# mcuBoard.net
KiCad netlist of a schematic drawn in EAGLE
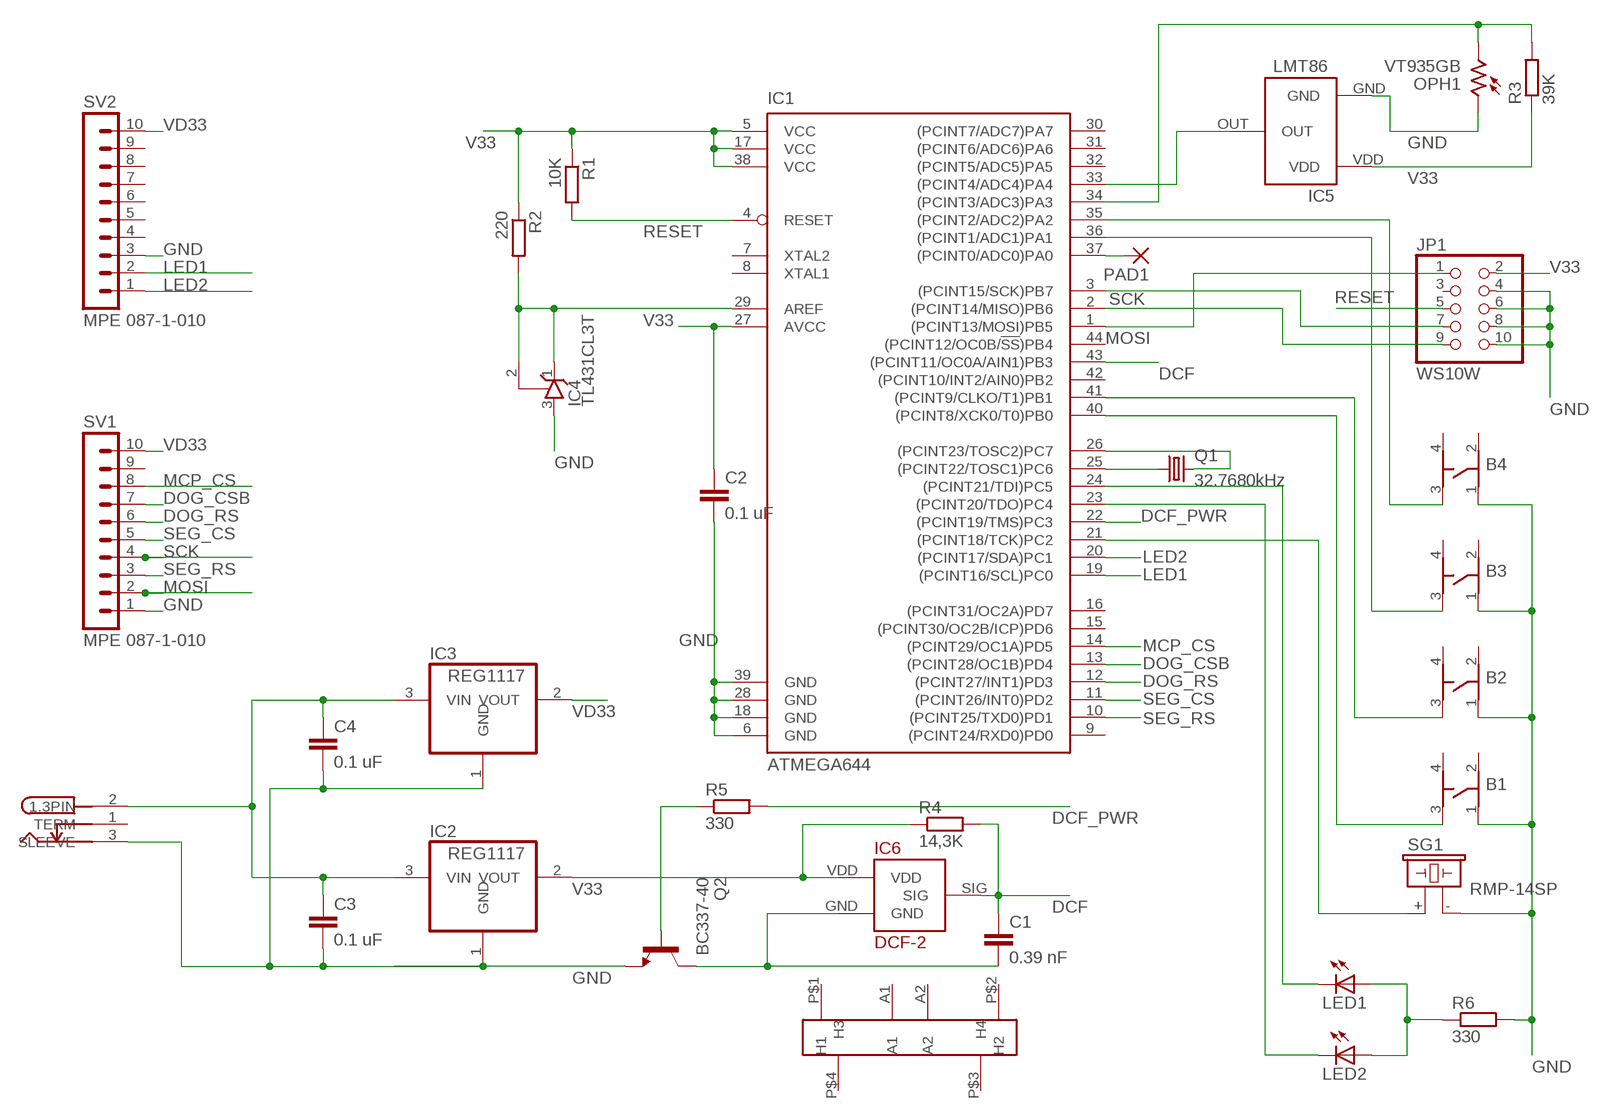
[diagram p0: schematic, sheet 1]

(export (version "E")
  (design (tool "Eeschema 10.0.6"))
  (components
    (comp (ref "B1")
      (value "BUTTON-D6X")
      (footprint "eagle-import:BUTTON-D6X")
      (libsource (lib "eagle-import") (part "BUTTON-D6X"))
    )
    (comp (ref "B2")
      (value "BUTTON-D6X")
      (footprint "eagle-import:BUTTON-D6X")
      (libsource (lib "eagle-import") (part "BUTTON-D6X"))
    )
    (comp (ref "B3")
      (value "BUTTON-D6X")
      (footprint "eagle-import:BUTTON-D6X")
      (libsource (lib "eagle-import") (part "BUTTON-D6X"))
    )
    (comp (ref "B4")
      (value "BUTTON-D6X")
      (footprint "eagle-import:BUTTON-D6X")
      (libsource (lib "eagle-import") (part "BUTTON-D6X"))
    )
    (comp (ref "C1")
      (value "0.39 nF")
      (footprint "eagle-import:C1206")
      (libsource (lib "eagle-import") (part "C-EUC1206"))
    )
    (comp (ref "C2")
      (value "0.1 uF")
      (footprint "eagle-import:C1206K")
      (libsource (lib "eagle-import") (part "C-EUC1206K"))
    )
    (comp (ref "C3")
      (value "0.1 uF")
      (footprint "eagle-import:C1206K")
      (libsource (lib "eagle-import") (part "C-EUC1206K"))
    )
    (comp (ref "C4")
      (value "0.1 uF")
      (footprint "eagle-import:C1206K")
      (libsource (lib "eagle-import") (part "C-EUC1206K"))
    )
    (comp (ref "IC1")
      (value "ATMEGA644")
      (footprint "eagle-import:TQFP44")
      (fields (field (name "MPN") "ATMEGA644PV-10AU"))
      (libsource (lib "eagle-import") (part "ATMEGA644A"))
    )
    (comp (ref "IC2")
      (value "REG1117")
      (footprint "eagle-import:SOT223")
      (libsource (lib "eagle-import") (part "REG1117"))
    )
    (comp (ref "IC3")
      (value "REG1117")
      (footprint "eagle-import:SOT223")
      (libsource (lib "eagle-import") (part "REG1117"))
    )
    (comp (ref "IC4")
      (value "TL431CL3T")
      (footprint "eagle-import:SOT23")
      (libsource (lib "eagle-import") (part "TL431CL3T"))
    )
    (comp (ref "IC5")
      (value "LMT86")
      (footprint "eagle-import:LMT86")
      (libsource (lib "eagle-import") (part "LMT86"))
    )
    (comp (ref "IC6")
      (value "DCF77")
      (footprint "eagle-import:DCF77")
      (libsource (lib "eagle-import") (part "DCF77"))
    )
    (comp (ref "JP1")
      (value "WS10W")
      (footprint "eagle-import:2X05")
      (libsource (lib "eagle-import") (part "PINHD-2X5"))
    )
    (comp (ref "LED1")
      (value "LED3MM")
      (footprint "eagle-import:LED3MM")
      (libsource (lib "eagle-import") (part "LED3MM"))
    )
    (comp (ref "LED2")
      (value "LED3MM")
      (footprint "eagle-import:LED3MM")
      (libsource (lib "eagle-import") (part "LED3MM"))
    )
    (comp (ref "OPH1")
      (value "VT935GB")
      (footprint "eagle-import:VT900")
      (libsource (lib "eagle-import") (part "VT935GB"))
    )
    (comp (ref "PAD1")
      (value "1,6/0,8")
      (footprint "eagle-import:1,6_0,8")
      (libsource (lib "eagle-import") (part "1,6/0,8"))
    )
    (comp (ref "Q1")
      (value "32.7680kHz")
      (footprint "eagle-import:MC-306")
      (fields (field (name "MPN") "MC-306 60.0KHZ  100PPM ,12.5PF"))
      (libsource (lib "eagle-import") (part "MC-306"))
    )
    (comp (ref "Q2")
      (value "BC337-40")
      (footprint "eagle-import:TO92")
      (libsource (lib "eagle-import") (part "BC337-40"))
    )
    (comp (ref "R1")
      (value "10K")
      (footprint "eagle-import:M1206")
      (libsource (lib "eagle-import") (part "R-EU_M1206"))
    )
    (comp (ref "R2")
      (value "220")
      (footprint "eagle-import:M1206")
      (libsource (lib "eagle-import") (part "R-EU_M1206"))
    )
    (comp (ref "R3")
      (value "39K")
      (footprint "eagle-import:M1206")
      (libsource (lib "eagle-import") (part "R-EU_M1206"))
    )
    (comp (ref "R4")
      (value "14,3K")
      (footprint "eagle-import:R1206")
      (libsource (lib "eagle-import") (part "R-EU_R1206"))
    )
    (comp (ref "R5")
      (value "330")
      (footprint "eagle-import:R1206")
      (libsource (lib "eagle-import") (part "R-EU_R1206"))
    )
    (comp (ref "R6")
      (value "330")
      (footprint "eagle-import:M1206")
      (libsource (lib "eagle-import") (part "R-EU_M1206"))
    )
    (comp (ref "SG1")
      (value "RMP-14SP")
      (footprint "eagle-import:F_CM12P")
      (libsource (lib "eagle-import") (part "F/CM12P"))
    )
    (comp (ref "SV1")
      (value "MPE 087-1-010")
      (footprint "eagle-import:MA10-1")
      (libsource (lib "eagle-import") (part "MA10-1"))
    )
    (comp (ref "SV2")
      (value "MPE 087-1-010")
      (footprint "eagle-import:MA10-1")
      (libsource (lib "eagle-import") (part "MA10-1"))
    )
    (comp (ref "U$1")
      (value "DC-8N")
      (footprint "eagle-import:BUCHSE-1.3X3.75")
      (libsource (lib "eagle-import") (part "DC-8N"))
    )
    (comp (ref "U$2")
      (value "DCF77-ANT")
      (footprint "eagle-import:DCF77-ANT")
      (libsource (lib "eagle-import") (part "DCF77-ANT"))
    )
  )
  (nets
    (net (code "1") (name "/DCF") (class "Default")
      (node (ref "C1") (pin "1") (pinfunction "1_1") (pintype "passive"))
      (node (ref "IC1") (pin "43") (pinfunction "(PCINT11/OC0A/AIN1)PB3_43") (pintype "bidirectional"))
      (node (ref "IC6") (pin "SIG") (pinfunction "SIG_SIG") (pintype "bidirectional"))
      (node (ref "R4") (pin "2") (pinfunction "2_2") (pintype "passive"))
    )
    (net (code "2") (name "/DCF_PWR") (class "Default")
      (node (ref "IC1") (pin "22") (pinfunction "(PCINT19/TMS)PC3_22") (pintype "output"))
      (node (ref "R5") (pin "2") (pinfunction "2_2") (pintype "passive"))
    )
    (net (code "3") (name "/DOG_CSB") (class "Default")
      (node (ref "IC1") (pin "13") (pinfunction "(PCINT28/OC1B)PD4_13") (pintype "bidirectional"))
      (node (ref "SV1") (pin "7") (pinfunction "7_7") (pintype "passive"))
    )
    (net (code "4") (name "/DOG_RS") (class "Default")
      (node (ref "IC1") (pin "12") (pinfunction "(PCINT27/INT1)PD3_12") (pintype "bidirectional"))
      (node (ref "SV1") (pin "6") (pinfunction "6_6") (pintype "passive"))
    )
    (net (code "5") (name "/GND") (class "Default")
      (node (ref "B1") (pin "1") (pinfunction "1_1") (pintype "bidirectional"))
      (node (ref "B2") (pin "1") (pinfunction "1_1") (pintype "bidirectional"))
      (node (ref "B3") (pin "1") (pinfunction "1_1") (pintype "bidirectional"))
      (node (ref "B4") (pin "1") (pinfunction "1_1") (pintype "bidirectional"))
      (node (ref "C2") (pin "2") (pinfunction "2_2") (pintype "passive"))
      (node (ref "C3") (pin "2") (pinfunction "2_2") (pintype "passive"))
      (node (ref "C4") (pin "2") (pinfunction "2_2") (pintype "passive"))
      (node (ref "IC1") (pin "18") (pinfunction "GND_18") (pintype "power_in"))
      (node (ref "IC1") (pin "28") (pinfunction "GND_28") (pintype "power_in"))
      (node (ref "IC1") (pin "39") (pinfunction "GND_39") (pintype "power_in"))
      (node (ref "IC1") (pin "6") (pinfunction "GND_6") (pintype "power_in"))
      (node (ref "IC2") (pin "1") (pinfunction "GND_1") (pintype "power_in"))
      (node (ref "IC3") (pin "1") (pinfunction "GND_1") (pintype "power_in"))
      (node (ref "IC4") (pin "3") (pinfunction "A_3") (pintype "passive"))
      (node (ref "IC5") (pin "GND") (pinfunction "GND_GND") (pintype "power_in"))
      (node (ref "JP1") (pin "10") (pinfunction "10_10") (pintype "passive"))
      (node (ref "JP1") (pin "4") (pinfunction "4_4") (pintype "passive"))
      (node (ref "JP1") (pin "6") (pinfunction "6_6") (pintype "passive"))
      (node (ref "JP1") (pin "8") (pinfunction "8_8") (pintype "passive"))
      (node (ref "OPH1") (pin "1") (pinfunction "1_1") (pintype "passive"))
      (node (ref "Q2") (pin "1") (pinfunction "E_1") (pintype "passive"))
      (node (ref "R6") (pin "2") (pinfunction "2_2") (pintype "passive"))
      (node (ref "SG1") (pin "-") (pinfunction "2_-") (pintype "passive"))
      (node (ref "SV1") (pin "1") (pinfunction "1_1") (pintype "passive"))
      (node (ref "SV2") (pin "3") (pinfunction "3_3") (pintype "passive"))
      (node (ref "U$1") (pin "3") (pinfunction "SLEEVE_3") (pintype "power_in"))
    )
    (net (code "6") (name "/LED1") (class "Default")
      (node (ref "IC1") (pin "19") (pinfunction "(PCINT16/SCL)PC0_19") (pintype "output"))
      (node (ref "SV2") (pin "2") (pinfunction "2_2") (pintype "passive"))
    )
    (net (code "7") (name "/LED2") (class "Default")
      (node (ref "IC1") (pin "20") (pinfunction "(PCINT17/SDA)PC1_20") (pintype "output"))
      (node (ref "SV2") (pin "1") (pinfunction "1_1") (pintype "passive"))
    )
    (net (code "8") (name "/MCP_CS") (class "Default")
      (node (ref "IC1") (pin "14") (pinfunction "(PCINT29/OC1A)PD5_14") (pintype "bidirectional"))
      (node (ref "SV1") (pin "8") (pinfunction "8_8") (pintype "passive"))
    )
    (net (code "9") (name "/MOSI") (class "Default")
      (node (ref "IC1") (pin "1") (pinfunction "(PCINT13/MOSI)PB5_1") (pintype "bidirectional"))
      (node (ref "JP1") (pin "1") (pinfunction "1_1") (pintype "passive"))
      (node (ref "SV1") (pin "2") (pinfunction "2_2") (pintype "passive"))
    )
    (net (code "10") (name "/RESET") (class "Default")
      (node (ref "IC1") (pin "4") (pinfunction "RESET_4") (pintype "input"))
      (node (ref "JP1") (pin "5") (pinfunction "5_5") (pintype "passive"))
      (node (ref "R1") (pin "2") (pinfunction "2_2") (pintype "passive"))
    )
    (net (code "11") (name "/SCK") (class "Default")
      (node (ref "IC1") (pin "3") (pinfunction "(PCINT15/SCK)PB7_3") (pintype "bidirectional"))
      (node (ref "JP1") (pin "7") (pinfunction "7_7") (pintype "passive"))
      (node (ref "SV1") (pin "4") (pinfunction "4_4") (pintype "passive"))
    )
    (net (code "12") (name "/SEG_CS") (class "Default")
      (node (ref "IC1") (pin "11") (pinfunction "(PCINT26/INT0)PD2_11") (pintype "bidirectional"))
      (node (ref "SV1") (pin "5") (pinfunction "5_5") (pintype "passive"))
    )
    (net (code "13") (name "/SEG_RS") (class "Default")
      (node (ref "IC1") (pin "10") (pinfunction "(PCINT25/TXD0)PD1_10") (pintype "bidirectional"))
      (node (ref "SV1") (pin "3") (pinfunction "3_3") (pintype "passive"))
    )
    (net (code "14") (name "/V33") (class "Default")
      (node (ref "C2") (pin "1") (pinfunction "1_1") (pintype "passive"))
      (node (ref "IC1") (pin "17") (pinfunction "VCC_17") (pintype "power_in"))
      (node (ref "IC1") (pin "27") (pinfunction "AVCC_27") (pintype "power_in"))
      (node (ref "IC1") (pin "38") (pinfunction "VCC_38") (pintype "power_in"))
      (node (ref "IC1") (pin "5") (pinfunction "VCC_5") (pintype "power_in"))
      (node (ref "IC2") (pin "2") (pinfunction "VOUT_2") (pintype "output"))
      (node (ref "IC5") (pin "VDD") (pinfunction "VDD_VDD") (pintype "power_in"))
      (node (ref "IC6") (pin "VDD") (pinfunction "VDD_VDD") (pintype "power_in"))
      (node (ref "JP1") (pin "2") (pinfunction "2_2") (pintype "passive"))
      (node (ref "R1") (pin "1") (pinfunction "1_1") (pintype "passive"))
      (node (ref "R2") (pin "1") (pinfunction "1_1") (pintype "passive"))
      (node (ref "R3") (pin "1") (pinfunction "1_1") (pintype "passive"))
      (node (ref "R4") (pin "1") (pinfunction "1_1") (pintype "passive"))
    )
    (net (code "15") (name "/VD33") (class "Default")
      (node (ref "IC3") (pin "2") (pinfunction "VOUT_2") (pintype "output"))
      (node (ref "SV1") (pin "10") (pinfunction "10_10") (pintype "passive"))
      (node (ref "SV2") (pin "10") (pinfunction "10_10") (pintype "passive"))
    )
    (net (code "16") (name "Net-(IC1-(PCINT0{slash}ADC0)PA0)") (class "Default")
      (node (ref "IC1") (pin "37") (pinfunction "(PCINT0/ADC0)PA0_37") (pintype "bidirectional"))
      (node (ref "PAD1") (pin "1") (pinfunction "P_1") (pintype "passive"))
    )
    (net (code "17") (name "Net-(IC1-(PCINT1{slash}ADC1)PA1)") (class "Default")
      (node (ref "B3") (pin "3") (pinfunction "3_3") (pintype "bidirectional"))
      (node (ref "IC1") (pin "36") (pinfunction "(PCINT1/ADC1)PA1_36") (pintype "bidirectional"))
    )
    (net (code "18") (name "Net-(IC1-(PCINT2{slash}ADC2)PA2)") (class "Default")
      (node (ref "B4") (pin "3") (pinfunction "3_3") (pintype "bidirectional"))
      (node (ref "IC1") (pin "35") (pinfunction "(PCINT2/ADC2)PA2_35") (pintype "bidirectional"))
    )
    (net (code "19") (name "Net-(IC1-(PCINT3{slash}ADC3)PA3)") (class "Default")
      (node (ref "IC1") (pin "34") (pinfunction "(PCINT3/ADC3)PA3_34") (pintype "bidirectional"))
      (node (ref "OPH1") (pin "2") (pinfunction "2_2") (pintype "passive"))
      (node (ref "R3") (pin "2") (pinfunction "2_2") (pintype "passive"))
    )
    (net (code "20") (name "Net-(IC1-(PCINT4{slash}ADC4)PA4)") (class "Default")
      (node (ref "IC1") (pin "33") (pinfunction "(PCINT4/ADC4)PA4_33") (pintype "bidirectional"))
      (node (ref "IC5") (pin "OUT") (pinfunction "OUT_OUT") (pintype "bidirectional"))
    )
    (net (code "21") (name "Net-(IC1-(PCINT8{slash}XCK0{slash}T0)PB0)") (class "Default")
      (node (ref "B1") (pin "3") (pinfunction "3_3") (pintype "bidirectional"))
      (node (ref "IC1") (pin "40") (pinfunction "(PCINT8/XCK0/T0)PB0_40") (pintype "bidirectional"))
    )
    (net (code "22") (name "Net-(IC1-(PCINT9{slash}CLKO{slash}T1)PB1)") (class "Default")
      (node (ref "B2") (pin "3") (pinfunction "3_3") (pintype "bidirectional"))
      (node (ref "IC1") (pin "41") (pinfunction "(PCINT9/CLKO/T1)PB1_41") (pintype "bidirectional"))
    )
    (net (code "23") (name "Net-(IC1-(PCINT14{slash}MISO)PB6)") (class "Default")
      (node (ref "IC1") (pin "2") (pinfunction "(PCINT14/MISO)PB6_2") (pintype "bidirectional"))
      (node (ref "JP1") (pin "9") (pinfunction "9_9") (pintype "passive"))
    )
    (net (code "24") (name "Net-(IC1-(PCINT18{slash}TCK)PC2)") (class "Default")
      (node (ref "IC1") (pin "21") (pinfunction "(PCINT18/TCK)PC2_21") (pintype "output"))
      (node (ref "SG1") (pin "+") (pinfunction "1_+") (pintype "passive"))
    )
    (net (code "25") (name "Net-(IC1-(PCINT20{slash}TDO)PC4)") (class "Default")
      (node (ref "IC1") (pin "23") (pinfunction "(PCINT20/TDO)PC4_23") (pintype "output"))
      (node (ref "LED2") (pin "K") (pinfunction "C_K") (pintype "passive"))
    )
    (net (code "26") (name "Net-(IC1-(PCINT21{slash}TDI)PC5)") (class "Default")
      (node (ref "IC1") (pin "24") (pinfunction "(PCINT21/TDI)PC5_24") (pintype "output"))
      (node (ref "LED1") (pin "K") (pinfunction "C_K") (pintype "passive"))
    )
    (net (code "27") (name "Net-(IC1-(PCINT22{slash}TOSC1)PC6)") (class "Default")
      (node (ref "IC1") (pin "25") (pinfunction "(PCINT22/TOSC1)PC6_25") (pintype "output"))
      (node (ref "Q1") (pin "1") (pinfunction "1_1") (pintype "passive"))
    )
    (net (code "28") (name "Net-(IC1-(PCINT23{slash}TOSC2)PC7)") (class "Default")
      (node (ref "IC1") (pin "26") (pinfunction "(PCINT23/TOSC2)PC7_26") (pintype "output"))
      (node (ref "Q1") (pin "4") (pinfunction "2_4") (pintype "passive"))
    )
    (net (code "29") (name "Net-(IC1-AREF)") (class "Default")
      (node (ref "IC1") (pin "29") (pinfunction "AREF_29") (pintype "passive"))
      (node (ref "IC4") (pin "1") (pinfunction "C_1") (pintype "passive"))
      (node (ref "IC4") (pin "2") (pinfunction "R_2") (pintype "passive"))
      (node (ref "R2") (pin "2") (pinfunction "2_2") (pintype "passive"))
    )
    (net (code "30") (name "Net-(IC2-VIN)") (class "Default")
      (node (ref "C3") (pin "1") (pinfunction "1_1") (pintype "passive"))
      (node (ref "C4") (pin "1") (pinfunction "1_1") (pintype "passive"))
      (node (ref "IC2") (pin "3") (pinfunction "VIN_3") (pintype "input"))
      (node (ref "IC3") (pin "3") (pinfunction "VIN_3") (pintype "input"))
      (node (ref "U$1") (pin "2") (pinfunction "1.3PIN_2") (pintype "power_in"))
    )
    (net (code "31") (name "Net-(LED1-PadA)") (class "Default")
      (node (ref "LED1") (pin "A") (pinfunction "A_A") (pintype "passive"))
      (node (ref "LED2") (pin "A") (pinfunction "A_A") (pintype "passive"))
      (node (ref "R6") (pin "1") (pinfunction "1_1") (pintype "passive"))
    )
    (net (code "32") (name "Net-(Q2-B)") (class "Default")
      (node (ref "Q2") (pin "2") (pinfunction "B_2") (pintype "passive"))
      (node (ref "R5") (pin "1") (pinfunction "1_1") (pintype "passive"))
    )
    (net (code "33") (name "Net-(Q2-C)") (class "Default")
      (node (ref "C1") (pin "2") (pinfunction "2_2") (pintype "passive"))
      (node (ref "IC6") (pin "GND") (pinfunction "GND_GND") (pintype "power_in"))
      (node (ref "Q2") (pin "3") (pinfunction "C_3") (pintype "passive"))
    )
    (net (code "34") (name "unconnected-(B1-Pad2)") (class "Default")
      (node (ref "B1") (pin "2") (pinfunction "2_2") (pintype "bidirectional"))
    )
    (net (code "35") (name "unconnected-(B1-Pad4)") (class "Default")
      (node (ref "B1") (pin "4") (pinfunction "4_4") (pintype "bidirectional"))
    )
    (net (code "36") (name "unconnected-(B2-Pad2)") (class "Default")
      (node (ref "B2") (pin "2") (pinfunction "2_2") (pintype "bidirectional"))
    )
    (net (code "37") (name "unconnected-(B2-Pad4)") (class "Default")
      (node (ref "B2") (pin "4") (pinfunction "4_4") (pintype "bidirectional"))
    )
    (net (code "38") (name "unconnected-(B3-Pad2)") (class "Default")
      (node (ref "B3") (pin "2") (pinfunction "2_2") (pintype "bidirectional"))
    )
    (net (code "39") (name "unconnected-(B3-Pad4)") (class "Default")
      (node (ref "B3") (pin "4") (pinfunction "4_4") (pintype "bidirectional"))
    )
    (net (code "40") (name "unconnected-(B4-Pad2)") (class "Default")
      (node (ref "B4") (pin "2") (pinfunction "2_2") (pintype "bidirectional"))
    )
    (net (code "41") (name "unconnected-(B4-Pad4)") (class "Default")
      (node (ref "B4") (pin "4") (pinfunction "4_4") (pintype "bidirectional"))
    )
    (net (code "42") (name "unconnected-(IC1-(PCINT5{slash}ADC5)PA5-Pad32)") (class "Default")
      (node (ref "IC1") (pin "32") (pinfunction "(PCINT5/ADC5)PA5_32") (pintype "bidirectional"))
    )
    (net (code "43") (name "unconnected-(IC1-(PCINT6{slash}ADC6)PA6-Pad31)") (class "Default")
      (node (ref "IC1") (pin "31") (pinfunction "(PCINT6/ADC6)PA6_31") (pintype "bidirectional"))
    )
    (net (code "44") (name "unconnected-(IC1-(PCINT7{slash}ADC7)PA7-Pad30)") (class "Default")
      (node (ref "IC1") (pin "30") (pinfunction "(PCINT7/ADC7)PA7_30") (pintype "bidirectional"))
    )
    (net (code "45") (name "unconnected-(IC1-(PCINT10{slash}INT2{slash}AIN0)PB2-Pad42)") (class "Default")
      (node (ref "IC1") (pin "42") (pinfunction "(PCINT10/INT2/AIN0)PB2_42") (pintype "bidirectional"))
    )
    (net (code "46") (name "unconnected-(IC1-(PCINT12{slash}OC0B{slash}~{SS})PB4-Pad44)") (class "Default")
      (node (ref "IC1") (pin "44") (pinfunction "(PCINT12/OC0B/~{SS})PB4_44") (pintype "bidirectional"))
    )
    (net (code "47") (name "unconnected-(IC1-(PCINT24{slash}RXD0)PD0-Pad9)") (class "Default")
      (node (ref "IC1") (pin "9") (pinfunction "(PCINT24/RXD0)PD0_9") (pintype "bidirectional"))
    )
    (net (code "48") (name "unconnected-(IC1-(PCINT30{slash}OC2B{slash}ICP)PD6-Pad15)") (class "Default")
      (node (ref "IC1") (pin "15") (pinfunction "(PCINT30/OC2B/ICP)PD6_15") (pintype "bidirectional"))
    )
    (net (code "49") (name "unconnected-(IC1-(PCINT31{slash}OC2A)PD7-Pad16)") (class "Default")
      (node (ref "IC1") (pin "16") (pinfunction "(PCINT31/OC2A)PD7_16") (pintype "bidirectional"))
    )
    (net (code "50") (name "unconnected-(IC1-XTAL1-Pad8)") (class "Default")
      (node (ref "IC1") (pin "8") (pinfunction "XTAL1_8") (pintype "bidirectional"))
    )
    (net (code "51") (name "unconnected-(IC1-XTAL2-Pad7)") (class "Default")
      (node (ref "IC1") (pin "7") (pinfunction "XTAL2_7") (pintype "bidirectional"))
    )
    (net (code "52") (name "unconnected-(JP1-Pad3)") (class "Default")
      (node (ref "JP1") (pin "3") (pinfunction "3_3") (pintype "passive"))
    )
    (net (code "53") (name "unconnected-(SV1-Pad9)") (class "Default")
      (node (ref "SV1") (pin "9") (pinfunction "9_9") (pintype "passive"))
    )
    (net (code "54") (name "unconnected-(SV2-Pad4)") (class "Default")
      (node (ref "SV2") (pin "4") (pinfunction "4_4") (pintype "passive"))
    )
    (net (code "55") (name "unconnected-(SV2-Pad5)") (class "Default")
      (node (ref "SV2") (pin "5") (pinfunction "5_5") (pintype "passive"))
    )
    (net (code "56") (name "unconnected-(SV2-Pad6)") (class "Default")
      (node (ref "SV2") (pin "6") (pinfunction "6_6") (pintype "passive"))
    )
    (net (code "57") (name "unconnected-(SV2-Pad7)") (class "Default")
      (node (ref "SV2") (pin "7") (pinfunction "7_7") (pintype "passive"))
    )
    (net (code "58") (name "unconnected-(SV2-Pad8)") (class "Default")
      (node (ref "SV2") (pin "8") (pinfunction "8_8") (pintype "passive"))
    )
    (net (code "59") (name "unconnected-(SV2-Pad9)") (class "Default")
      (node (ref "SV2") (pin "9") (pinfunction "9_9") (pintype "passive"))
    )
    (net (code "60") (name "unconnected-(U$1-TERM-Pad1)") (class "Default")
      (node (ref "U$1") (pin "1") (pinfunction "TERM_1") (pintype "bidirectional"))
    )
    (net (code "61") (name "unconnected-(U$2-H1-PadP$1)") (class "Default")
      (node (ref "U$2") (pin "P$1") (pinfunction "H1_P$1") (pintype "bidirectional"))
    )
    (net (code "62") (name "unconnected-(U$2-H2-PadP$2)") (class "Default")
      (node (ref "U$2") (pin "P$2") (pinfunction "H2_P$2") (pintype "bidirectional"))
    )
    (net (code "63") (name "unconnected-(U$2-H3-PadP$4)") (class "Default")
      (node (ref "U$2") (pin "P$4") (pinfunction "H3_P$4") (pintype "bidirectional"))
    )
    (net (code "64") (name "unconnected-(U$2-H4-PadP$3)") (class "Default")
      (node (ref "U$2") (pin "P$3") (pinfunction "H4_P$3") (pintype "bidirectional"))
    )
    (net (code "65") (name "unconnected-(U$2-PadA1)") (class "Default")
      (node (ref "U$2") (pin "A1") (pinfunction "A1_A1") (pintype "bidirectional"))
    )
    (net (code "66") (name "unconnected-(U$2-PadA2)") (class "Default")
      (node (ref "U$2") (pin "A2") (pinfunction "A2_A2") (pintype "bidirectional"))
    )
  )
)
